# B2B_connectors.net
KiCad netlist of a schematic drawn in Altium Designer
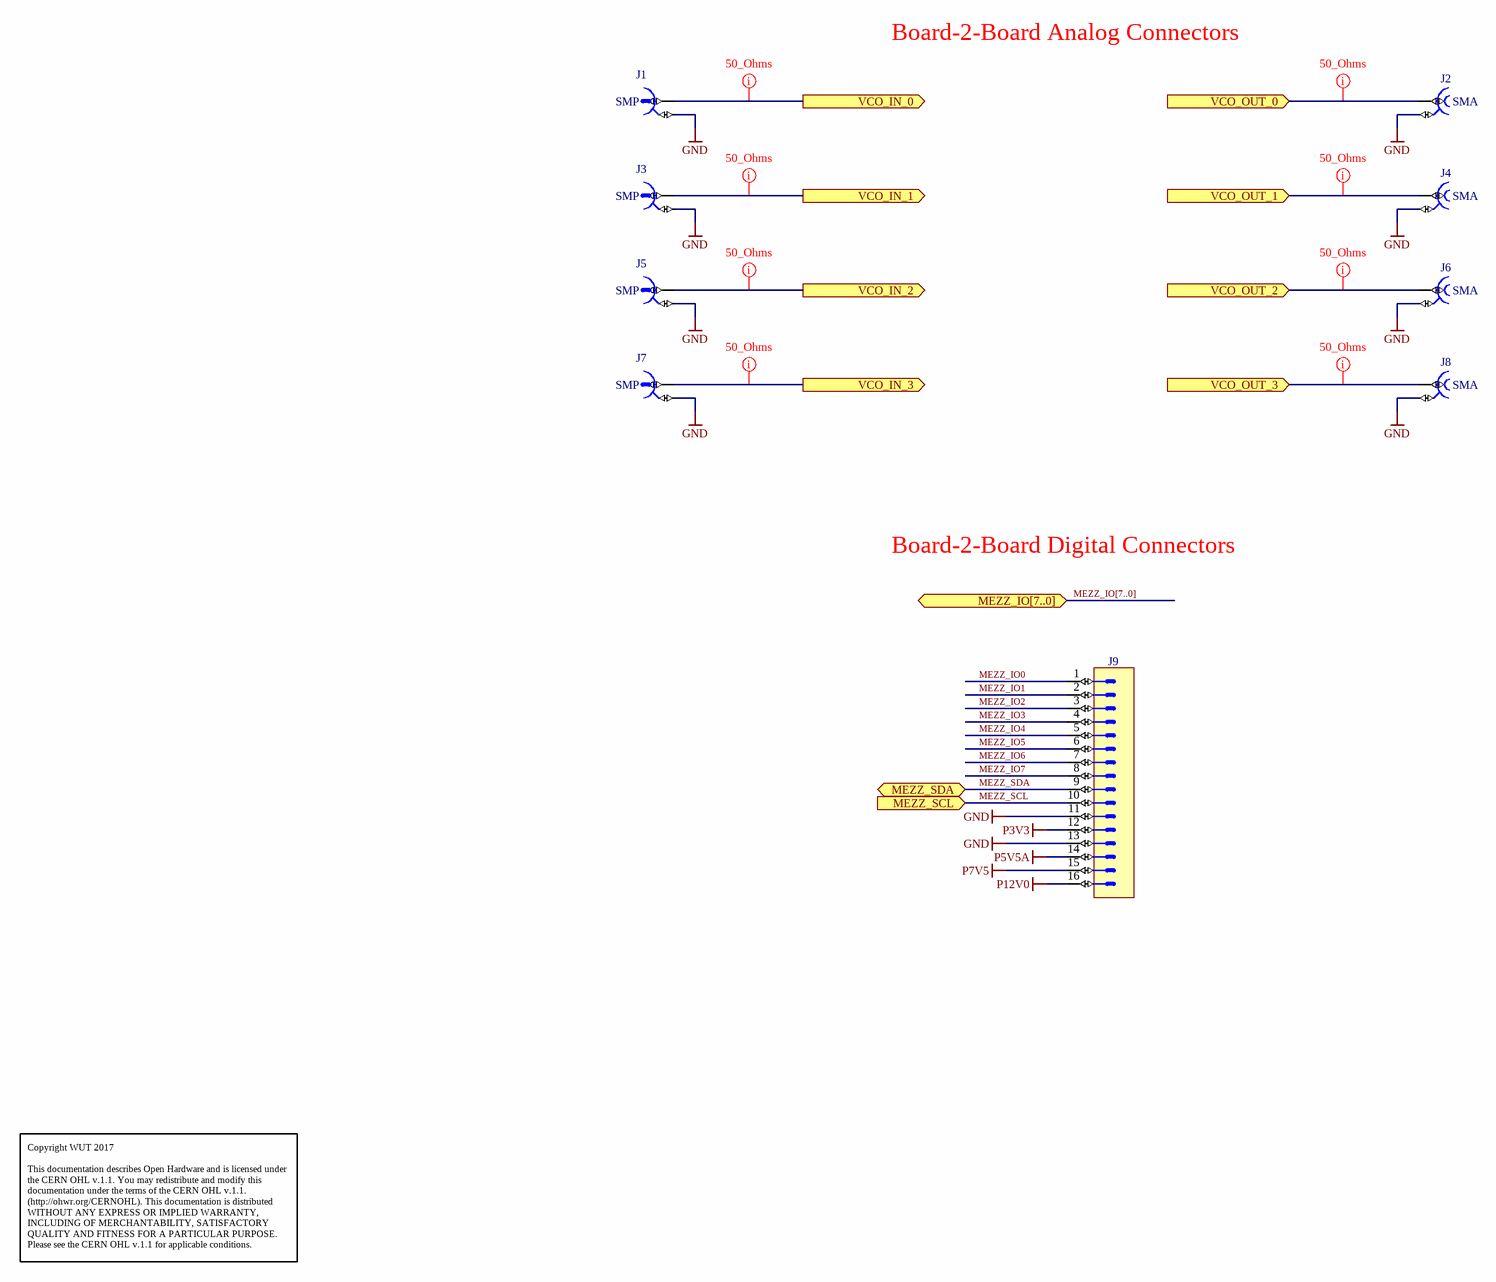
[diagram p0: B2B_connectors.SchDoc]

(export (version "E")
  (design (tool "Eeschema 10.0.6"))
  (components
    (comp (ref "J1")
      (value "SMP")
      (footprint "MOLEX_85305-0232")
      (fields
        (field (name "PART NUMBER") "MOLEX_85305-0232")
        (field (name "MANUFACTURER") "MOLEX")
        (field (name "MANUFACTURER PART NUMBER") "85305-0232")
        (field (name "AUTHOR") "CERN DEM JMW")
      )
      (libsource (lib "Connectors") (part "Coax_1Male_1Shield"))
    )
    (comp (ref "J2")
      (value "SMA")
      (footprint "TELEGARTNER_J01151A0451")
      (fields
        (field (name "PART NUMBER") "TELEGARTNER_J01151A0451")
        (field (name "MANUFACTURER") "TELEGARTNER")
        (field (name "MANUFACTURER PART NUMBER") "J01151A0451")
        (field (name "AUTHOR") "CERN DEM JLC")
      )
      (libsource (lib "Connectors") (part "Coax_1Female_1Shield"))
    )
    (comp (ref "J3")
      (value "SMP")
      (footprint "MOLEX_85305-0232")
      (fields
        (field (name "PART NUMBER") "MOLEX_85305-0232")
        (field (name "MANUFACTURER") "MOLEX")
        (field (name "MANUFACTURER PART NUMBER") "85305-0232")
        (field (name "AUTHOR") "CERN DEM JMW")
      )
      (libsource (lib "Connectors") (part "Coax_1Male_1Shield"))
    )
    (comp (ref "J4")
      (value "SMA")
      (footprint "TELEGARTNER_J01151A0451")
      (fields
        (field (name "PART NUMBER") "TELEGARTNER_J01151A0451")
        (field (name "MANUFACTURER") "TELEGARTNER")
        (field (name "MANUFACTURER PART NUMBER") "J01151A0451")
        (field (name "AUTHOR") "CERN DEM JLC")
      )
      (libsource (lib "Connectors") (part "Coax_1Female_1Shield"))
    )
    (comp (ref "J5")
      (value "SMP")
      (footprint "MOLEX_85305-0232")
      (fields
        (field (name "PART NUMBER") "MOLEX_85305-0232")
        (field (name "MANUFACTURER") "MOLEX")
        (field (name "MANUFACTURER PART NUMBER") "85305-0232")
        (field (name "AUTHOR") "CERN DEM JMW")
      )
      (libsource (lib "Connectors") (part "Coax_1Male_1Shield"))
    )
    (comp (ref "J6")
      (value "SMA")
      (footprint "TELEGARTNER_J01151A0451")
      (fields
        (field (name "PART NUMBER") "TELEGARTNER_J01151A0451")
        (field (name "MANUFACTURER") "TELEGARTNER")
        (field (name "MANUFACTURER PART NUMBER") "J01151A0451")
        (field (name "AUTHOR") "CERN DEM JLC")
      )
      (libsource (lib "Connectors") (part "Coax_1Female_1Shield"))
    )
    (comp (ref "J7")
      (value "SMP")
      (footprint "MOLEX_85305-0232")
      (fields
        (field (name "PART NUMBER") "MOLEX_85305-0232")
        (field (name "MANUFACTURER") "MOLEX")
        (field (name "MANUFACTURER PART NUMBER") "85305-0232")
        (field (name "AUTHOR") "CERN DEM JMW")
      )
      (libsource (lib "Connectors") (part "Coax_1Male_1Shield"))
    )
    (comp (ref "J8")
      (value "SMA")
      (footprint "TELEGARTNER_J01151A0451")
      (fields
        (field (name "PART NUMBER") "TELEGARTNER_J01151A0451")
        (field (name "MANUFACTURER") "TELEGARTNER")
        (field (name "MANUFACTURER PART NUMBER") "J01151A0451")
        (field (name "AUTHOR") "CERN DEM JLC")
      )
      (libsource (lib "Connectors") (part "Coax_1Female_1Shield"))
    )
    (comp (ref "J9")
      (value "Header 16")
      (footprint "3M_N2516-6002RB")
      (description "Connector 16 Male")
      (fields
        (field (name "PART NUMBER") "3M_N2516-6002RB")
        (field (name "MANUFACTURER") "3M")
        (field (name "AUTHOR") "CERN DEM JLC")
      )
      (libsource (lib "Connectors") (part "Connector 16 Male"))
    )
  )
  (nets
    (net (code "1") (name "/MEZZ_IO0") (class "Default")
      (node (ref "J9") (pin "1") (pinfunction "1_1") (pintype "bidirectional"))
    )
    (net (code "2") (name "/MEZZ_IO1") (class "Default")
      (node (ref "J9") (pin "2") (pinfunction "2_2") (pintype "bidirectional"))
    )
    (net (code "3") (name "/MEZZ_IO2") (class "Default")
      (node (ref "J9") (pin "3") (pinfunction "3_3") (pintype "bidirectional"))
    )
    (net (code "4") (name "/MEZZ_IO3") (class "Default")
      (node (ref "J9") (pin "4") (pinfunction "4_4") (pintype "bidirectional"))
    )
    (net (code "5") (name "/MEZZ_IO4") (class "Default")
      (node (ref "J9") (pin "5") (pinfunction "5_5") (pintype "bidirectional"))
    )
    (net (code "6") (name "/MEZZ_IO5") (class "Default")
      (node (ref "J9") (pin "6") (pinfunction "6_6") (pintype "bidirectional"))
    )
    (net (code "7") (name "/MEZZ_IO6") (class "Default")
      (node (ref "J9") (pin "7") (pinfunction "7_7") (pintype "bidirectional"))
    )
    (net (code "8") (name "/MEZZ_IO7") (class "Default")
      (node (ref "J9") (pin "8") (pinfunction "8_8") (pintype "bidirectional"))
    )
    (net (code "10") (name "/MEZZ_SCL") (class "Default")
      (node (ref "J9") (pin "10") (pinfunction "10_10") (pintype "bidirectional"))
    )
    (net (code "11") (name "/MEZZ_SDA") (class "Default")
      (node (ref "J9") (pin "9") (pinfunction "9_9") (pintype "bidirectional"))
    )
    (net (code "12") (name "/VCO_IN_0") (class "Default")
      (node (ref "J1") (pin "1") (pinfunction "1_1") (pintype "bidirectional"))
    )
    (net (code "13") (name "/VCO_IN_1") (class "Default")
      (node (ref "J3") (pin "1") (pinfunction "1_1") (pintype "bidirectional"))
    )
    (net (code "14") (name "/VCO_IN_2") (class "Default")
      (node (ref "J5") (pin "1") (pinfunction "1_1") (pintype "bidirectional"))
    )
    (net (code "15") (name "/VCO_IN_3") (class "Default")
      (node (ref "J7") (pin "1") (pinfunction "1_1") (pintype "bidirectional"))
    )
    (net (code "16") (name "/VCO_OUT_0") (class "Default")
      (node (ref "J2") (pin "1") (pinfunction "1_1") (pintype "bidirectional"))
    )
    (net (code "17") (name "/VCO_OUT_1") (class "Default")
      (node (ref "J4") (pin "1") (pinfunction "1_1") (pintype "bidirectional"))
    )
    (net (code "18") (name "/VCO_OUT_2") (class "Default")
      (node (ref "J6") (pin "1") (pinfunction "1_1") (pintype "bidirectional"))
    )
    (net (code "19") (name "/VCO_OUT_3") (class "Default")
      (node (ref "J8") (pin "1") (pinfunction "1_1") (pintype "bidirectional"))
    )
    (net (code "20") (name "GND") (class "Default")
      (node (ref "J1") (pin "2") (pinfunction "2_2") (pintype "bidirectional"))
      (node (ref "J2") (pin "2") (pinfunction "2_2") (pintype "bidirectional"))
      (node (ref "J3") (pin "2") (pinfunction "2_2") (pintype "bidirectional"))
      (node (ref "J4") (pin "2") (pinfunction "2_2") (pintype "bidirectional"))
      (node (ref "J5") (pin "2") (pinfunction "2_2") (pintype "bidirectional"))
      (node (ref "J6") (pin "2") (pinfunction "2_2") (pintype "bidirectional"))
      (node (ref "J7") (pin "2") (pinfunction "2_2") (pintype "bidirectional"))
      (node (ref "J8") (pin "2") (pinfunction "2_2") (pintype "bidirectional"))
      (node (ref "J9") (pin "11") (pinfunction "11_11") (pintype "bidirectional"))
      (node (ref "J9") (pin "13") (pinfunction "13_13") (pintype "bidirectional"))
    )
    (net (code "21") (name "P3V3") (class "Default")
      (node (ref "J9") (pin "12") (pinfunction "12_12") (pintype "bidirectional"))
    )
    (net (code "22") (name "P5V5A") (class "Default")
      (node (ref "J9") (pin "14") (pinfunction "14_14") (pintype "bidirectional"))
    )
    (net (code "23") (name "P7V5") (class "Default")
      (node (ref "J9") (pin "15") (pinfunction "15_15") (pintype "bidirectional"))
    )
    (net (code "24") (name "P12V0") (class "Default")
      (node (ref "J9") (pin "16") (pinfunction "16_16") (pintype "bidirectional"))
    )
  )
)
